# oledrgb.net
KiCad netlist of a schematic drawn in EAGLE
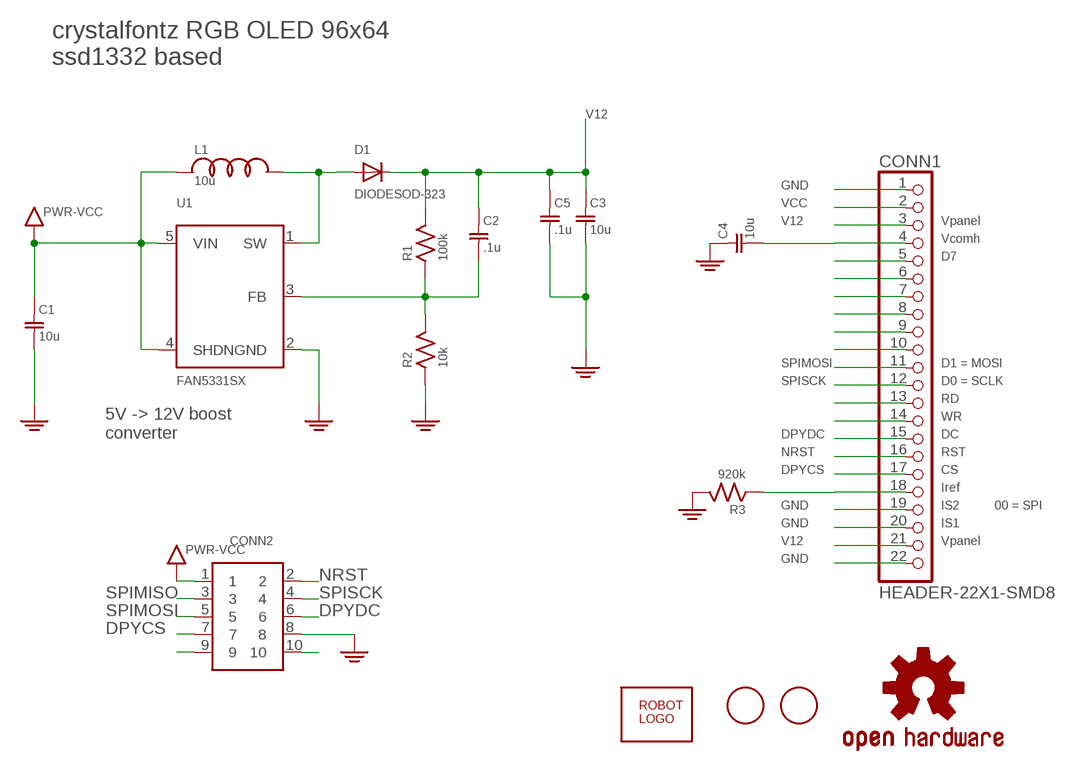
[diagram p0: schematic, sheet 1]

(export (version "E")
  (design (tool "Eeschema 10.0.6"))
  (components
    (comp (ref "C1")
      (value "10u")
      (footprint "eagle-import:SMD0603")
      (libsource (lib "eagle-import") (part "C0603"))
    )
    (comp (ref "C2")
      (value ".1u")
      (footprint "eagle-import:SMD0603")
      (libsource (lib "eagle-import") (part "C0603"))
    )
    (comp (ref "C3")
      (value "10u")
      (footprint "eagle-import:SMD0603")
      (libsource (lib "eagle-import") (part "C0603"))
    )
    (comp (ref "C4")
      (value "10u")
      (footprint "eagle-import:SMD0603")
      (libsource (lib "eagle-import") (part "C0603"))
    )
    (comp (ref "C5")
      (value ".1u")
      (footprint "eagle-import:SMD0603")
      (libsource (lib "eagle-import") (part "C0603"))
    )
    (comp (ref "CONN1")
      (value "HEADER-22X1-SMD8")
      (footprint "eagle-import:HEADER-22X1-SMD8")
      (libsource (lib "eagle-import") (part "HEADER-22X1-SMD8"))
    )
    (comp (ref "CONN2")
      (value "HEADER-5X2-PTH")
      (footprint "eagle-import:HEADER-5X2-PTH")
      (libsource (lib "eagle-import") (part "HEADER-5X2-PTH"))
    )
    (comp (ref "D1")
      (value "DIODESOD-323")
      (footprint "eagle-import:SOD-323")
      (libsource (lib "eagle-import") (part "DIODESOD-323"))
    )
    (comp (ref "L1")
      (value "10u")
      (footprint "eagle-import:SMD0603")
      (libsource (lib "eagle-import") (part "LSMD0603"))
    )
    (comp (ref "LOGO1")
      (value "OSHW-LOGOS")
      (footprint "eagle-import:OSHW-LOGO-S")
      (libsource (lib "eagle-import") (part "OSHW-LOGOS"))
    )
    (comp (ref "R1")
      (value "100k")
      (footprint "eagle-import:SMD0603")
      (libsource (lib "eagle-import") (part "R0603"))
    )
    (comp (ref "R2")
      (value "10k")
      (footprint "eagle-import:SMD0603")
      (libsource (lib "eagle-import") (part "R0603"))
    )
    (comp (ref "R3")
      (value "920k")
      (footprint "eagle-import:SMD0603")
      (libsource (lib "eagle-import") (part "R0603"))
    )
    (comp (ref "U$1")
      (value "ROBOTMAN-LOGO2")
      (footprint "eagle-import:ROBOTMAN-LOGO2")
      (libsource (lib "eagle-import") (part "ROBOTMAN-LOGO2"))
    )
    (comp (ref "U$2")
      (value "FIDUCIAL")
      (footprint "eagle-import:FIDUCIAL_1MM")
      (libsource (lib "eagle-import") (part "FIDUCIAL"))
    )
    (comp (ref "U$3")
      (value "FIDUCIAL")
      (footprint "eagle-import:FIDUCIAL_1MM")
      (libsource (lib "eagle-import") (part "FIDUCIAL"))
    )
    (comp (ref "U1")
      (value "FAN5331SX")
      (footprint "eagle-import:SOT23-5")
      (libsource (lib "eagle-import") (part "FAN5331"))
    )
  )
  (nets
    (net (code "1") (name "/DPYCS") (class "Default")
      (node (ref "CONN1") (pin "17") (pinfunction "17_17") (pintype "passive"))
      (node (ref "CONN2") (pin "7") (pinfunction "7_7") (pintype "passive"))
    )
    (net (code "2") (name "/DPYDC") (class "Default")
      (node (ref "CONN1") (pin "15") (pinfunction "15_15") (pintype "passive"))
      (node (ref "CONN2") (pin "6") (pinfunction "6_6") (pintype "passive"))
    )
    (net (code "3") (name "/NRST") (class "Default")
      (node (ref "CONN1") (pin "16") (pinfunction "16_16") (pintype "passive"))
      (node (ref "CONN2") (pin "2") (pinfunction "2_2") (pintype "passive"))
    )
    (net (code "4") (name "/SPIMISO") (class "Default")
      (node (ref "CONN2") (pin "3") (pinfunction "3_3") (pintype "passive"))
    )
    (net (code "5") (name "/SPIMOSI") (class "Default")
      (node (ref "CONN1") (pin "11") (pinfunction "11_11") (pintype "passive"))
      (node (ref "CONN2") (pin "5") (pinfunction "5_5") (pintype "passive"))
    )
    (net (code "6") (name "/SPISCK") (class "Default")
      (node (ref "CONN1") (pin "12") (pinfunction "12_12") (pintype "passive"))
      (node (ref "CONN2") (pin "4") (pinfunction "4_4") (pintype "passive"))
    )
    (net (code "7") (name "/V12") (class "Default")
      (node (ref "C2") (pin "1") (pinfunction "P$1_1") (pintype "passive"))
      (node (ref "C3") (pin "1") (pinfunction "P$1_1") (pintype "passive"))
      (node (ref "C5") (pin "1") (pinfunction "P$1_1") (pintype "passive"))
      (node (ref "CONN1") (pin "21") (pinfunction "21_21") (pintype "passive"))
      (node (ref "CONN1") (pin "3") (pinfunction "3_3") (pintype "passive"))
      (node (ref "D1") (pin "C") (pinfunction "C_C") (pintype "passive"))
      (node (ref "R1") (pin "2") (pinfunction "P$2_2") (pintype "passive"))
    )
    (net (code "8") (name "Net-(C2-P$2)") (class "Default")
      (node (ref "C2") (pin "2") (pinfunction "P$2_2") (pintype "passive"))
      (node (ref "R1") (pin "1") (pinfunction "P$1_1") (pintype "passive"))
      (node (ref "R2") (pin "2") (pinfunction "P$2_2") (pintype "passive"))
      (node (ref "U1") (pin "3") (pinfunction "FB_3") (pintype "bidirectional"))
    )
    (net (code "9") (name "Net-(C4-P$2)") (class "Default")
      (node (ref "C4") (pin "2") (pinfunction "P$2_2") (pintype "passive"))
      (node (ref "CONN1") (pin "4") (pinfunction "4_4") (pintype "passive"))
    )
    (net (code "10") (name "Net-(L1-P$2)") (class "Default")
      (node (ref "D1") (pin "A") (pinfunction "A_A") (pintype "passive"))
      (node (ref "L1") (pin "2") (pinfunction "P$2_2") (pintype "passive"))
      (node (ref "U1") (pin "1") (pinfunction "SW_1") (pintype "bidirectional"))
    )
    (net (code "11") (name "Net-(R3-P$1)") (class "Default")
      (node (ref "CONN1") (pin "18") (pinfunction "18_18") (pintype "passive"))
      (node (ref "R3") (pin "1") (pinfunction "P$1_1") (pintype "passive"))
    )
    (net (code "12") (name "PWR-GND") (class "Default")
      (node (ref "C1") (pin "2") (pinfunction "P$2_2") (pintype "passive"))
      (node (ref "C3") (pin "2") (pinfunction "P$2_2") (pintype "passive"))
      (node (ref "C4") (pin "1") (pinfunction "P$1_1") (pintype "passive"))
      (node (ref "C5") (pin "2") (pinfunction "P$2_2") (pintype "passive"))
      (node (ref "CONN1") (pin "1") (pinfunction "1_1") (pintype "passive"))
      (node (ref "CONN1") (pin "19") (pinfunction "19_19") (pintype "passive"))
      (node (ref "CONN1") (pin "20") (pinfunction "20_20") (pintype "passive"))
      (node (ref "CONN1") (pin "22") (pinfunction "22_22") (pintype "passive"))
      (node (ref "CONN2") (pin "8") (pinfunction "8_8") (pintype "passive"))
      (node (ref "R2") (pin "1") (pinfunction "P$1_1") (pintype "passive"))
      (node (ref "R3") (pin "2") (pinfunction "P$2_2") (pintype "passive"))
      (node (ref "U1") (pin "2") (pinfunction "GND_2") (pintype "bidirectional"))
    )
    (net (code "13") (name "PWR-VCC") (class "Default")
      (node (ref "C1") (pin "1") (pinfunction "P$1_1") (pintype "passive"))
      (node (ref "CONN1") (pin "2") (pinfunction "2_2") (pintype "passive"))
      (node (ref "CONN2") (pin "1") (pinfunction "1_1") (pintype "passive"))
      (node (ref "L1") (pin "1") (pinfunction "P$1_1") (pintype "passive"))
      (node (ref "U1") (pin "4") (pinfunction "SHDN_4") (pintype "bidirectional"))
      (node (ref "U1") (pin "5") (pinfunction "VIN_5") (pintype "bidirectional"))
    )
    (net (code "14") (name "unconnected-(CONN1-Pad5)") (class "Default")
      (node (ref "CONN1") (pin "5") (pinfunction "5_5") (pintype "passive"))
    )
    (net (code "15") (name "unconnected-(CONN1-Pad6)") (class "Default")
      (node (ref "CONN1") (pin "6") (pinfunction "6_6") (pintype "passive"))
    )
    (net (code "16") (name "unconnected-(CONN1-Pad7)") (class "Default")
      (node (ref "CONN1") (pin "7") (pinfunction "7_7") (pintype "passive"))
    )
    (net (code "17") (name "unconnected-(CONN1-Pad8)") (class "Default")
      (node (ref "CONN1") (pin "8") (pinfunction "8_8") (pintype "passive"))
    )
    (net (code "18") (name "unconnected-(CONN1-Pad9)") (class "Default")
      (node (ref "CONN1") (pin "9") (pinfunction "9_9") (pintype "passive"))
    )
    (net (code "19") (name "unconnected-(CONN1-Pad10)") (class "Default")
      (node (ref "CONN1") (pin "10") (pinfunction "10_10") (pintype "passive"))
    )
    (net (code "20") (name "unconnected-(CONN1-Pad13)") (class "Default")
      (node (ref "CONN1") (pin "13") (pinfunction "13_13") (pintype "passive"))
    )
    (net (code "21") (name "unconnected-(CONN1-Pad14)") (class "Default")
      (node (ref "CONN1") (pin "14") (pinfunction "14_14") (pintype "passive"))
    )
    (net (code "22") (name "unconnected-(CONN2-Pad9)") (class "Default")
      (node (ref "CONN2") (pin "9") (pinfunction "9_9") (pintype "passive"))
    )
    (net (code "23") (name "unconnected-(CONN2-Pad10)") (class "Default")
      (node (ref "CONN2") (pin "10") (pinfunction "10_10") (pintype "passive"))
    )
  )
)
